# USB_Type_C_Connector_ESD.net
KiCad netlist of a schematic drawn in Altium Designer
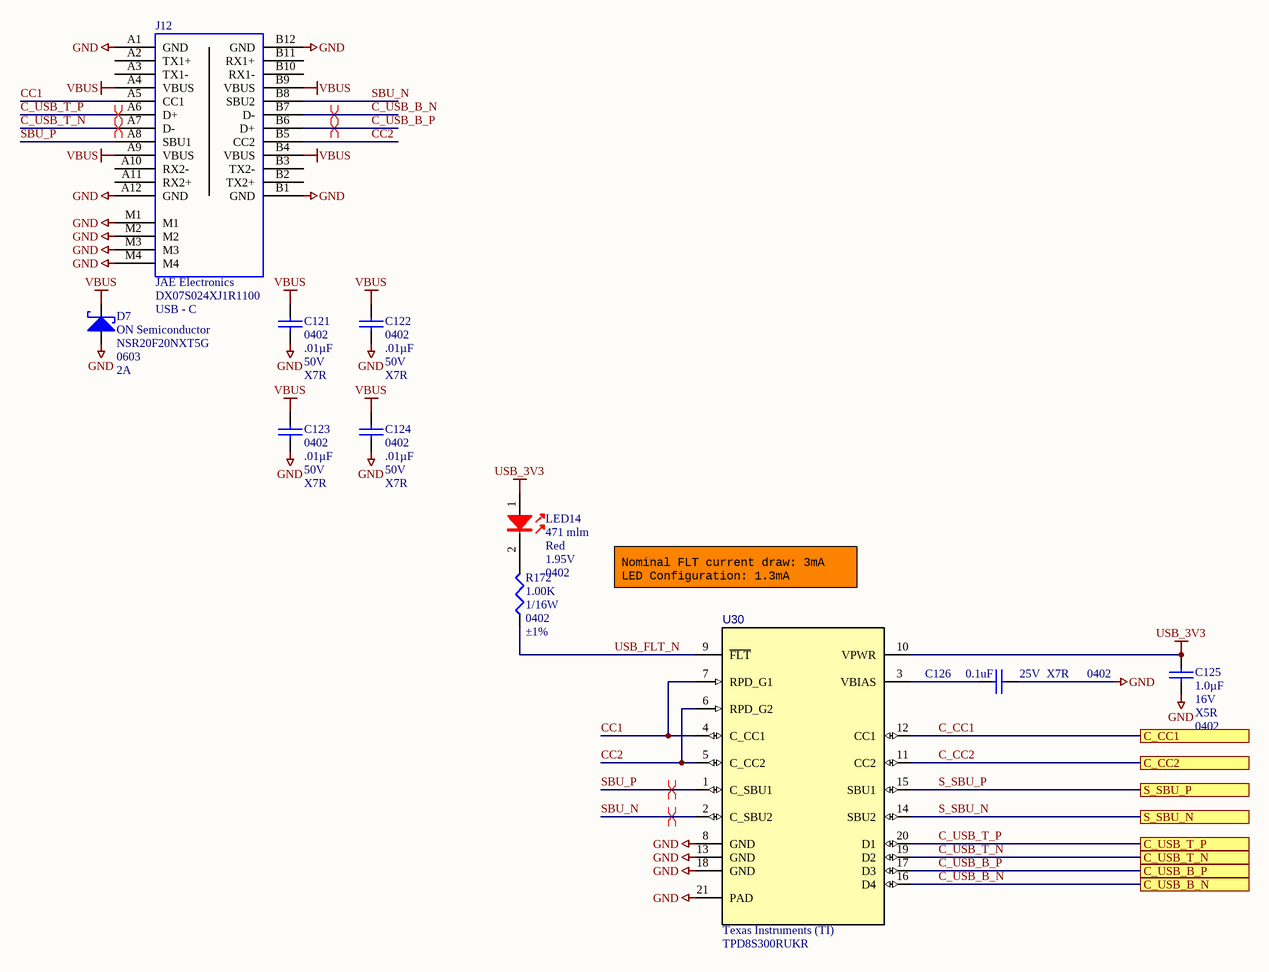
[diagram p0: USB Type C Connector ESD.SchDoc]

(export (version "E")
  (design (tool "Eeschema 10.0.6"))
  (components
    (comp (ref "C121")
      (value "10000pF")
      (footprint "C_ERA-0402")
      (description "CAP CERAMIC .01UF 50V X7R 0402")
      (fields
        (field (name "MANUFACTURER") "Murata Electronics North America")
        (field (name "MANUFACTURER PART NUMBER") "GRM155R71H103KA88D")
        (field (name "PACKAGE / CASE") "0402")
        (field (name "CAPACITANCE") ".01µF")
        (field (name "VOLTAGE - RATED") "50V")
        (field (name "TEMPERATURE COEFFICIENT") "X7R")
      )
      (libsource (lib "Main LibraryX") (part "C_0402_10000PF_50V"))
    )
    (comp (ref "C122")
      (value "10000pF")
      (footprint "C_ERA-0402")
      (description "CAP CERAMIC .01UF 50V X7R 0402")
      (fields
        (field (name "MANUFACTURER") "Murata Electronics North America")
        (field (name "MANUFACTURER PART NUMBER") "GRM155R71H103KA88D")
        (field (name "PACKAGE / CASE") "0402")
        (field (name "CAPACITANCE") ".01µF")
        (field (name "VOLTAGE - RATED") "50V")
        (field (name "TEMPERATURE COEFFICIENT") "X7R")
      )
      (libsource (lib "Main LibraryX") (part "C_0402_10000PF_50V"))
    )
    (comp (ref "C123")
      (value "10000pF")
      (footprint "C_ERA-0402")
      (description "CAP CERAMIC .01UF 50V X7R 0402")
      (fields
        (field (name "MANUFACTURER") "Murata Electronics North America")
        (field (name "MANUFACTURER PART NUMBER") "GRM155R71H103KA88D")
        (field (name "PACKAGE / CASE") "0402")
        (field (name "CAPACITANCE") ".01µF")
        (field (name "VOLTAGE - RATED") "50V")
        (field (name "TEMPERATURE COEFFICIENT") "X7R")
      )
      (libsource (lib "Main LibraryX") (part "C_0402_10000PF_50V"))
    )
    (comp (ref "C124")
      (value "10000pF")
      (footprint "C_ERA-0402")
      (description "CAP CERAMIC .01UF 50V X7R 0402")
      (fields
        (field (name "MANUFACTURER") "Murata Electronics North America")
        (field (name "MANUFACTURER PART NUMBER") "GRM155R71H103KA88D")
        (field (name "PACKAGE / CASE") "0402")
        (field (name "CAPACITANCE") ".01µF")
        (field (name "VOLTAGE - RATED") "50V")
        (field (name "TEMPERATURE COEFFICIENT") "X7R")
      )
      (libsource (lib "Main LibraryX") (part "C_0402_10000PF_50V"))
    )
    (comp (ref "C125")
      (value "1.0uF")
      (footprint "C_0402")
      (description "CAP CER 1.0UF 16V X5R 0402")
      (fields
        (field (name "TOLERANCE") "10%")
        (field (name "CAPACITANCE") "1.0µF")
        (field (name "VOLTAGE - RATED") "16V")
        (field (name "TEMPERATURE COEFFICIENT") "X5R")
        (field (name "PACKAGE / CASE") "0402")
        (field (name "VOLTAGE") "16V")
      )
      (libsource (lib "Main LibraryX") (part "C_0402_1.0UF_16V"))
    )
    (comp (ref "C126")
      (value "C_0402_0.1UF_25V")
      (footprint "C_0402")
      (description "CAP CER 0.1UF 25V X6S 0402")
      (fields
        (field (name "TOLERANCE") "10%")
        (field (name "CAPACITANCE") "0.1uF")
        (field (name "VOLTAGE - RATED") "25V")
        (field (name "TEMPERATURE COEFFICIENT") "X7R")
        (field (name "PACKAGE / CASE") "0402")
      )
      (libsource (lib "Cospan Design") (part "C_0402_0.1UF_25V"))
    )
    (comp (ref "D7")
      (value "D_SCHOTT_30V_2A_XDFN")
      (footprint "DSN2_0603")
      (description "Diode Schottky 30V 2A (DC) Surface Mount 2-DSN (1.6x.80)")
      (fields
        (field (name "MANUFACTURER") "ON Semiconductor")
        (field (name "MANUFACTURER PART NUMBER") "NSR20F20NXT5G")
        (field (name "CASE/PACKAGE") "0603")
        (field (name "AVERAGE RECTIFIED CURRENT") "2A")
      )
      (libsource (lib "Cospan Design") (part "D_SCHOTT_30V_2A_XDFN"))
    )
    (comp (ref "J12")
      (value "J_DX07S024XJ1R1100")
      (footprint "DX07S024XJ1R1100")
      (description "CONN RCPT USB C TOP MNT HYBRID")
      (fields
        (field (name "MANUFACTURER") "JAE Electronics")
        (field (name "MANUFACTURER PART NUMBER") "DX07S024XJ1R1100")
        (field (name "CONNECTOR TYPE") "USB - C")
      )
      (libsource (lib "Cospan Design") (part "J_DX07S024XJ1R1100"))
    )
    (comp (ref "LED14")
      (value "LED_RED_0402")
      (footprint "DIOM1005X07L_RED")
      (description "LED 1X0.5MM 630NM RD WTR CLR SMD")
      (fields
        (field (name "MANUFACTURER") "Kingbright Corp")
        (field (name "MANUFACTURER PART NUMBER") "APHHS1005SURCK")
        (field (name "LUMINOUS FLUX @ CURRENT - TEST") "471 mlm")
        (field (name "COLOR") "Red")
        (field (name "VOLTAGE - FORWARD (VF) TYP") "1.95V")
        (field (name "PACKAGE / CASE") "0402")
      )
      (libsource (lib "Main Library") (part "LED_RED_0402"))
    )
    (comp (ref "R172")
      (value "1.0k Ohms")
      (footprint "R_0402")
      (description "RES 1.00K OHM 1/16W 1% 0402 SMD")
      (fields
        (field (name "MANUFACTURER") "Yageo")
        (field (name "MANUFACTURER PART NUMBER") "RC0402FR-071KL")
        (field (name "RESISTANCE IN OHMS") "1.00K")
        (field (name "POWER (WATTS)") "1/16W")
        (field (name "CASE") "0402")
        (field (name "TOLERANCE") "±1%")
      )
      (libsource (lib "Main Library") (part "R_0402_1.0K"))
    )
    (comp (ref "U30")
      (value "U_TPD8S300RUK")
      (footprint "RUK0020B")
      (fields
        (field (name "MANUFACTURER") "Texas Instruments (TI)")
        (field (name "MANUFACTURER PART NUMBER") "TPD8S300RUKR")
      )
      (libsource (lib "Cospan Design") (part "U_TPD8S300RUK"))
    )
  )
  (nets
    (net (code "1") (name "/CC1") (class "Default")
      (node (ref "J12") (pin "A5") (pinfunction "CC1_A5") (pintype "passive"))
      (node (ref "U30") (pin "4") (pinfunction "C_CC1_4") (pintype "bidirectional"))
      (node (ref "U30") (pin "7") (pinfunction "RPD_G1_7") (pintype "input"))
    )
    (net (code "2") (name "/CC2") (class "Default")
      (node (ref "J12") (pin "B5") (pinfunction "CC2_B5") (pintype "passive"))
      (node (ref "U30") (pin "5") (pinfunction "C_CC2_5") (pintype "bidirectional"))
      (node (ref "U30") (pin "6") (pinfunction "RPD_G2_6") (pintype "input"))
    )
    (net (code "3") (name "/C_CC1") (class "Default")
      (node (ref "U30") (pin "12") (pinfunction "CC1_12") (pintype "bidirectional"))
    )
    (net (code "4") (name "/C_CC2") (class "Default")
      (node (ref "U30") (pin "11") (pinfunction "CC2_11") (pintype "bidirectional"))
    )
    (net (code "5") (name "/C_USB_B_N") (class "Default")
      (node (ref "J12") (pin "B7") (pinfunction "D-_B7") (pintype "passive"))
      (node (ref "U30") (pin "16") (pinfunction "D4_16") (pintype "bidirectional"))
    )
    (net (code "6") (name "/C_USB_B_P") (class "Default")
      (node (ref "J12") (pin "B6") (pinfunction "D+_B6") (pintype "passive"))
      (node (ref "U30") (pin "17") (pinfunction "D3_17") (pintype "bidirectional"))
    )
    (net (code "7") (name "/C_USB_T_N") (class "Default")
      (node (ref "J12") (pin "A7") (pinfunction "D-_A7") (pintype "passive"))
      (node (ref "U30") (pin "19") (pinfunction "D2_19") (pintype "bidirectional"))
    )
    (net (code "8") (name "/C_USB_T_P") (class "Default")
      (node (ref "J12") (pin "A6") (pinfunction "D+_A6") (pintype "passive"))
      (node (ref "U30") (pin "20") (pinfunction "D1_20") (pintype "bidirectional"))
    )
    (net (code "9") (name "/SBU_N") (class "Default")
      (node (ref "J12") (pin "B8") (pinfunction "SBU2_B8") (pintype "passive"))
      (node (ref "U30") (pin "2") (pinfunction "C_SBU2_2") (pintype "bidirectional"))
    )
    (net (code "10") (name "/SBU_P") (class "Default")
      (node (ref "J12") (pin "A8") (pinfunction "SBU1_A8") (pintype "passive"))
      (node (ref "U30") (pin "1") (pinfunction "C_SBU1_1") (pintype "bidirectional"))
    )
    (net (code "11") (name "/S_SBU_N") (class "Default")
      (node (ref "U30") (pin "14") (pinfunction "SBU2_14") (pintype "bidirectional"))
    )
    (net (code "12") (name "/S_SBU_P") (class "Default")
      (node (ref "U30") (pin "15") (pinfunction "SBU1_15") (pintype "bidirectional"))
    )
    (net (code "13") (name "/USB_FLT_N") (class "Default")
      (node (ref "R172") (pin "2") (pinfunction "2_2") (pintype "passive"))
      (node (ref "U30") (pin "9") (pinfunction "FLT_9") (pintype "open_collector"))
    )
    (net (code "14") (name "GND") (class "Default")
      (node (ref "C121") (pin "1") (pinfunction "1_1") (pintype "passive"))
      (node (ref "C122") (pin "1") (pinfunction "1_1") (pintype "passive"))
      (node (ref "C123") (pin "1") (pinfunction "1_1") (pintype "passive"))
      (node (ref "C124") (pin "1") (pinfunction "1_1") (pintype "passive"))
      (node (ref "C125") (pin "1") (pinfunction "1_1") (pintype "passive"))
      (node (ref "C126") (pin "1") (pinfunction "1_1") (pintype "passive"))
      (node (ref "D7") (pin "2") (pinfunction "A_2") (pintype "passive"))
      (node (ref "J12") (pin "A1") (pinfunction "GND_A1") (pintype "passive"))
      (node (ref "J12") (pin "A12") (pinfunction "GND_A12") (pintype "passive"))
      (node (ref "J12") (pin "B1") (pinfunction "GND_B1") (pintype "passive"))
      (node (ref "J12") (pin "B12") (pinfunction "GND_B12") (pintype "passive"))
      (node (ref "J12") (pin "M1") (pinfunction "M1_M1") (pintype "passive"))
      (node (ref "J12") (pin "M2") (pinfunction "M2_M2") (pintype "passive"))
      (node (ref "J12") (pin "M3") (pinfunction "M3_M3") (pintype "passive"))
      (node (ref "J12") (pin "M4") (pinfunction "M4_M4") (pintype "passive"))
      (node (ref "U30") (pin "13") (pinfunction "GND_13") (pintype "power_in"))
      (node (ref "U30") (pin "18") (pinfunction "GND_18") (pintype "power_in"))
      (node (ref "U30") (pin "21") (pinfunction "PAD_21") (pintype "power_in"))
      (node (ref "U30") (pin "8") (pinfunction "GND_8") (pintype "power_in"))
    )
    (net (code "15") (name "Net-(LED14-Pad2)") (class "Default")
      (node (ref "LED14") (pin "2") (pinfunction "2_2") (pintype "passive"))
      (node (ref "R172") (pin "1") (pinfunction "1_1") (pintype "passive"))
    )
    (net (code "16") (name "Net-(U30-VBIAS)") (class "Default")
      (node (ref "C126") (pin "2") (pinfunction "2_2") (pintype "passive"))
      (node (ref "U30") (pin "3") (pinfunction "VBIAS_3") (pintype "power_in"))
    )
    (net (code "17") (name "USB_3V3") (class "Default")
      (node (ref "C125") (pin "2") (pinfunction "2_2") (pintype "passive"))
      (node (ref "LED14") (pin "1") (pinfunction "1_1") (pintype "passive"))
      (node (ref "U30") (pin "10") (pinfunction "VPWR_10") (pintype "power_in"))
    )
    (net (code "18") (name "VBUS") (class "Default")
      (node (ref "C121") (pin "2") (pinfunction "2_2") (pintype "passive"))
      (node (ref "C122") (pin "2") (pinfunction "2_2") (pintype "passive"))
      (node (ref "C123") (pin "2") (pinfunction "2_2") (pintype "passive"))
      (node (ref "C124") (pin "2") (pinfunction "2_2") (pintype "passive"))
      (node (ref "D7") (pin "1") (pinfunction "C_1") (pintype "passive"))
      (node (ref "J12") (pin "A4") (pinfunction "VBUS_A4") (pintype "passive"))
      (node (ref "J12") (pin "A9") (pinfunction "VBUS_A9") (pintype "passive"))
      (node (ref "J12") (pin "B4") (pinfunction "VBUS_B4") (pintype "passive"))
      (node (ref "J12") (pin "B9") (pinfunction "VBUS_B9") (pintype "passive"))
    )
    (net (code "19") (name "unconnected-(J12-RX1+-PadB11)") (class "Default")
      (node (ref "J12") (pin "B11") (pinfunction "RX1+_B11") (pintype "passive"))
    )
    (net (code "20") (name "unconnected-(J12-RX1--PadB10)") (class "Default")
      (node (ref "J12") (pin "B10") (pinfunction "RX1-_B10") (pintype "passive"))
    )
    (net (code "21") (name "unconnected-(J12-RX2+-PadA11)") (class "Default")
      (node (ref "J12") (pin "A11") (pinfunction "RX2+_A11") (pintype "passive"))
    )
    (net (code "22") (name "unconnected-(J12-RX2--PadA10)") (class "Default")
      (node (ref "J12") (pin "A10") (pinfunction "RX2-_A10") (pintype "passive"))
    )
    (net (code "23") (name "unconnected-(J12-TX1+-PadA2)") (class "Default")
      (node (ref "J12") (pin "A2") (pinfunction "TX1+_A2") (pintype "passive"))
    )
    (net (code "24") (name "unconnected-(J12-TX1--PadA3)") (class "Default")
      (node (ref "J12") (pin "A3") (pinfunction "TX1-_A3") (pintype "passive"))
    )
    (net (code "25") (name "unconnected-(J12-TX2+-PadB2)") (class "Default")
      (node (ref "J12") (pin "B2") (pinfunction "TX2+_B2") (pintype "passive"))
    )
    (net (code "26") (name "unconnected-(J12-TX2--PadB3)") (class "Default")
      (node (ref "J12") (pin "B3") (pinfunction "TX2-_B3") (pintype "passive"))
    )
  )
)
